# M705ok.net
KiCad netlist of a schematic drawn in EAGLE
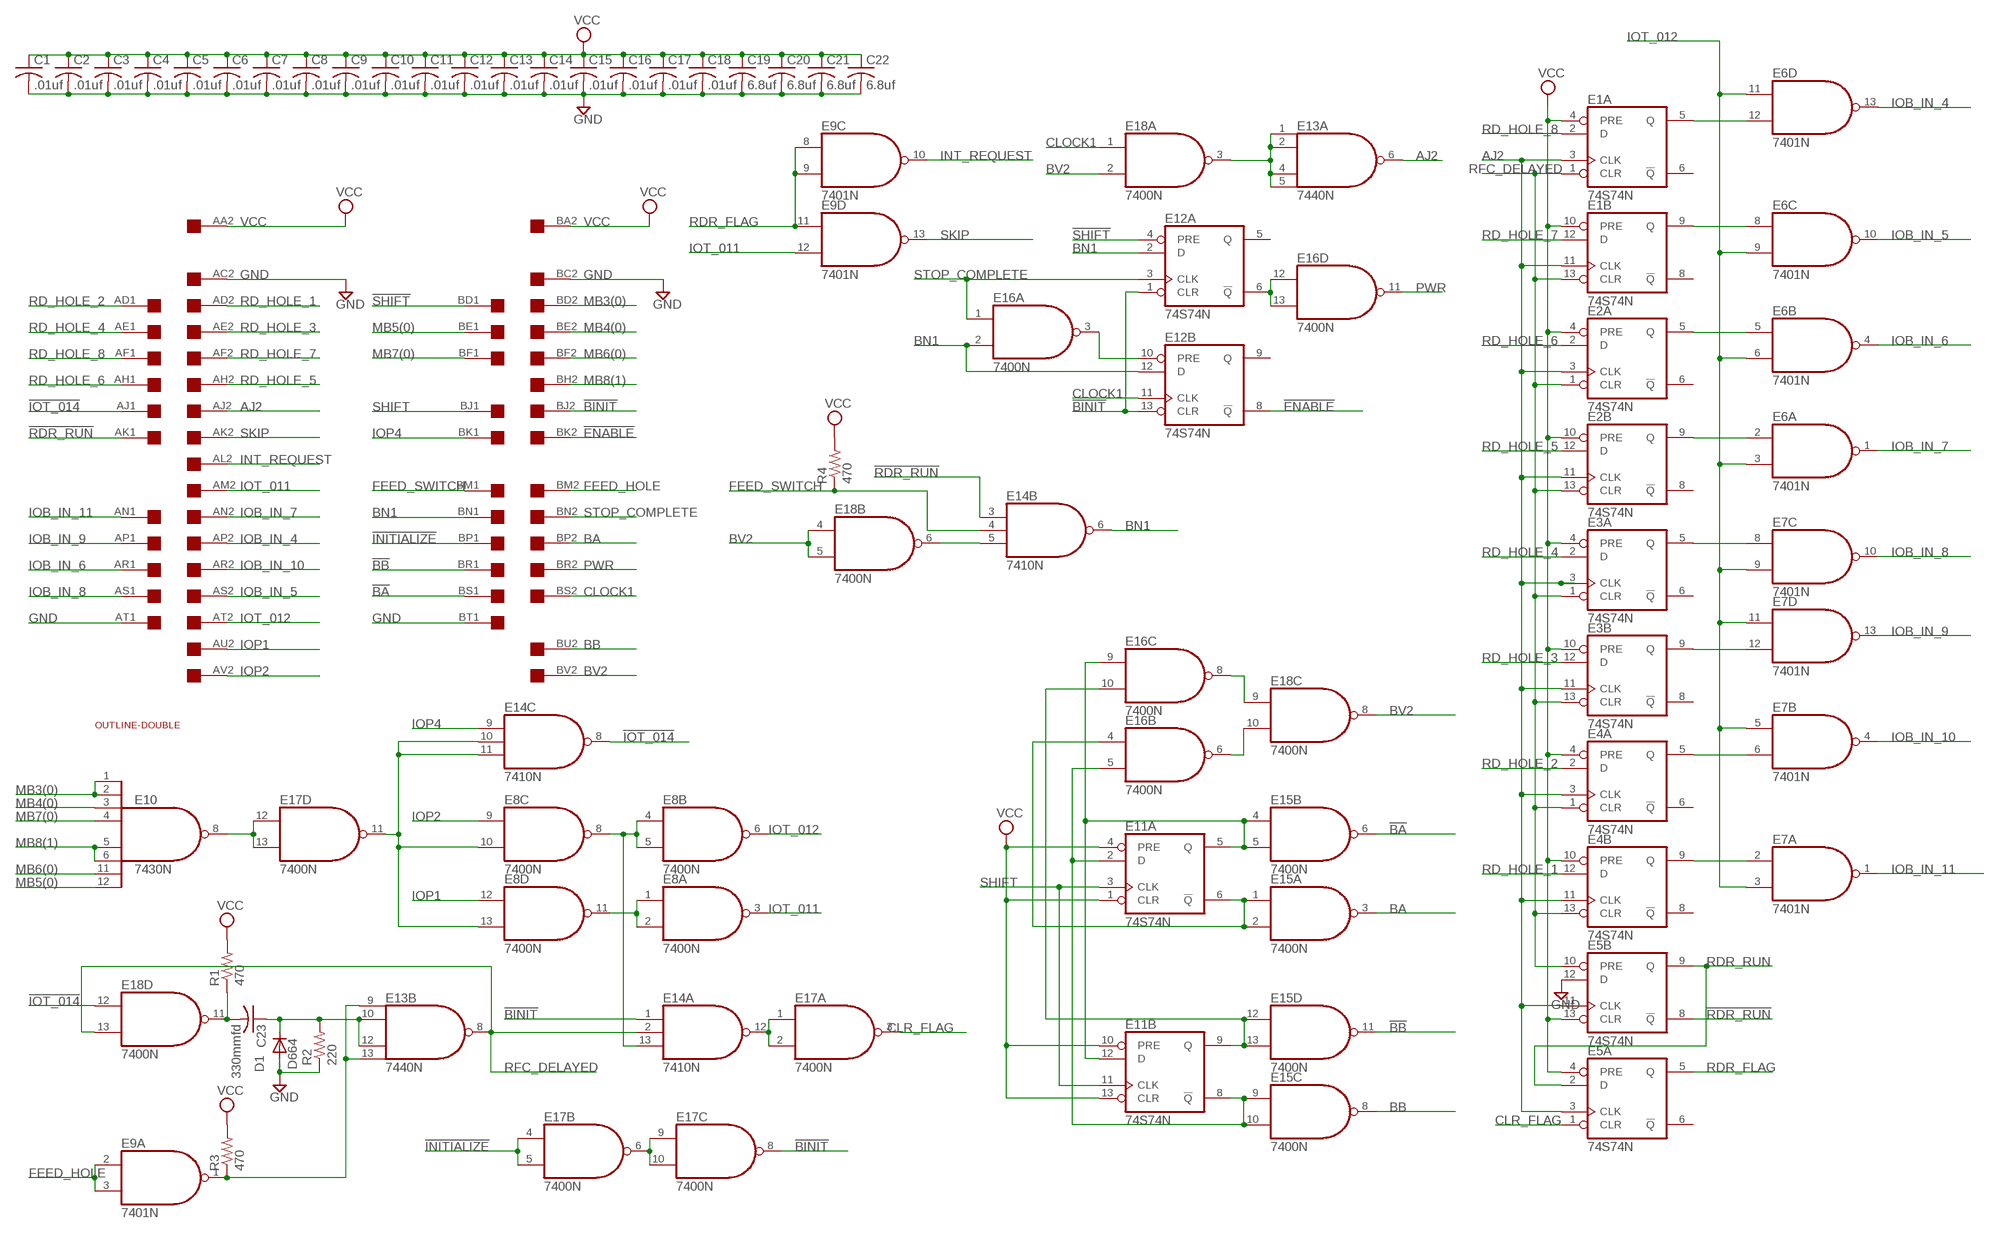
[diagram p0: schematic, sheet 1]

(export (version "E")
  (design (tool "Eeschema 10.0.6"))
  (components
    (comp (ref "C1")
      (value ".01uf")
      (footprint "eagle-import:C050-025X075")
      (libsource (lib "eagle-import") (part "C-US050-025X075"))
    )
    (comp (ref "C2")
      (value ".01uf")
      (footprint "eagle-import:C050-025X075")
      (libsource (lib "eagle-import") (part "C-US050-025X075"))
    )
    (comp (ref "C3")
      (value ".01uf")
      (footprint "eagle-import:C050-025X075")
      (libsource (lib "eagle-import") (part "C-US050-025X075"))
    )
    (comp (ref "C4")
      (value ".01uf")
      (footprint "eagle-import:C050-025X075")
      (libsource (lib "eagle-import") (part "C-US050-025X075"))
    )
    (comp (ref "C5")
      (value ".01uf")
      (footprint "eagle-import:C050-025X075")
      (libsource (lib "eagle-import") (part "C-US050-025X075"))
    )
    (comp (ref "C6")
      (value ".01uf")
      (footprint "eagle-import:C050-025X075")
      (libsource (lib "eagle-import") (part "C-US050-025X075"))
    )
    (comp (ref "C7")
      (value ".01uf")
      (footprint "eagle-import:C050-025X075")
      (libsource (lib "eagle-import") (part "C-US050-025X075"))
    )
    (comp (ref "C8")
      (value ".01uf")
      (footprint "eagle-import:C050-025X075")
      (libsource (lib "eagle-import") (part "C-US050-025X075"))
    )
    (comp (ref "C9")
      (value ".01uf")
      (footprint "eagle-import:C050-025X075")
      (libsource (lib "eagle-import") (part "C-US050-025X075"))
    )
    (comp (ref "C10")
      (value ".01uf")
      (footprint "eagle-import:C050-025X075")
      (libsource (lib "eagle-import") (part "C-US050-025X075"))
    )
    (comp (ref "C11")
      (value ".01uf")
      (footprint "eagle-import:C050-025X075")
      (libsource (lib "eagle-import") (part "C-US050-025X075"))
    )
    (comp (ref "C12")
      (value ".01uf")
      (footprint "eagle-import:C050-025X075")
      (libsource (lib "eagle-import") (part "C-US050-025X075"))
    )
    (comp (ref "C13")
      (value ".01uf")
      (footprint "eagle-import:C050-025X075")
      (libsource (lib "eagle-import") (part "C-US050-025X075"))
    )
    (comp (ref "C14")
      (value ".01uf")
      (footprint "eagle-import:C050-025X075")
      (libsource (lib "eagle-import") (part "C-US050-025X075"))
    )
    (comp (ref "C15")
      (value ".01uf")
      (footprint "eagle-import:C050-025X075")
      (libsource (lib "eagle-import") (part "C-US050-025X075"))
    )
    (comp (ref "C16")
      (value ".01uf")
      (footprint "eagle-import:C050-025X075")
      (libsource (lib "eagle-import") (part "C-US050-025X075"))
    )
    (comp (ref "C17")
      (value ".01uf")
      (footprint "eagle-import:C050-025X075")
      (libsource (lib "eagle-import") (part "C-US050-025X075"))
    )
    (comp (ref "C18")
      (value ".01uf")
      (footprint "eagle-import:C050-025X075")
      (libsource (lib "eagle-import") (part "C-US050-025X075"))
    )
    (comp (ref "C19")
      (value "6.8uf")
      (footprint "eagle-import:C150-054X183")
      (libsource (lib "eagle-import") (part "C-US150-054X183"))
    )
    (comp (ref "C20")
      (value "6.8uf")
      (footprint "eagle-import:C150-054X183")
      (libsource (lib "eagle-import") (part "C-US150-054X183"))
    )
    (comp (ref "C21")
      (value "6.8uf")
      (footprint "eagle-import:C150-054X183")
      (libsource (lib "eagle-import") (part "C-US150-054X183"))
    )
    (comp (ref "C22")
      (value "6.8uf")
      (footprint "eagle-import:C150-054X183")
      (libsource (lib "eagle-import") (part "C-US150-054X183"))
    )
    (comp (ref "C23")
      (value "330mmfd")
      (footprint "eagle-import:C050-025X075")
      (libsource (lib "eagle-import") (part "C-US050-025X075"))
    )
    (comp (ref "D1")
      (value "D664")
      (footprint "eagle-import:DO35-10")
      (libsource (lib "eagle-import") (part "1N4148DO35-10"))
    )
    (comp (ref "E1")
      (value "74S74N")
      (footprint "eagle-import:DIL14")
      (libsource (lib "eagle-import") (part "7474NS"))
    )
    (comp (ref "E2")
      (value "74S74N")
      (footprint "eagle-import:DIL14")
      (libsource (lib "eagle-import") (part "7474NS"))
    )
    (comp (ref "E3")
      (value "74S74N")
      (footprint "eagle-import:DIL14")
      (libsource (lib "eagle-import") (part "7474NS"))
    )
    (comp (ref "E4")
      (value "74S74N")
      (footprint "eagle-import:DIL14")
      (libsource (lib "eagle-import") (part "7474NS"))
    )
    (comp (ref "E5")
      (value "74S74N")
      (footprint "eagle-import:DIL14")
      (libsource (lib "eagle-import") (part "7474NS"))
    )
    (comp (ref "E6")
      (value "7401N")
      (footprint "eagle-import:DIL14")
      (libsource (lib "eagle-import") (part "7401NLS"))
    )
    (comp (ref "E7")
      (value "7401N")
      (footprint "eagle-import:DIL14")
      (libsource (lib "eagle-import") (part "7401NLS"))
    )
    (comp (ref "E8")
      (value "7400N")
      (footprint "eagle-import:DIL14")
      (libsource (lib "eagle-import") (part "7400N"))
    )
    (comp (ref "E9")
      (value "7401N")
      (footprint "eagle-import:DIL14")
      (libsource (lib "eagle-import") (part "7401NLS"))
    )
    (comp (ref "E10")
      (value "7430N")
      (footprint "eagle-import:DIL14")
      (libsource (lib "eagle-import") (part "7430N"))
    )
    (comp (ref "E11")
      (value "74S74N")
      (footprint "eagle-import:DIL14")
      (libsource (lib "eagle-import") (part "7474NS"))
    )
    (comp (ref "E12")
      (value "74S74N")
      (footprint "eagle-import:DIL14")
      (libsource (lib "eagle-import") (part "7474NS"))
    )
    (comp (ref "E13")
      (value "7440N")
      (footprint "eagle-import:DIL14")
      (libsource (lib "eagle-import") (part "7420NS"))
    )
    (comp (ref "E14")
      (value "7410N")
      (footprint "eagle-import:DIL14")
      (libsource (lib "eagle-import") (part "7410N"))
    )
    (comp (ref "E15")
      (value "7400N")
      (footprint "eagle-import:DIL14")
      (libsource (lib "eagle-import") (part "7400N"))
    )
    (comp (ref "E16")
      (value "7400N")
      (footprint "eagle-import:DIL14")
      (libsource (lib "eagle-import") (part "7400N"))
    )
    (comp (ref "E17")
      (value "7400N")
      (footprint "eagle-import:DIL14")
      (libsource (lib "eagle-import") (part "7400N"))
    )
    (comp (ref "E18")
      (value "7400N")
      (footprint "eagle-import:DIL14")
      (libsource (lib "eagle-import") (part "7400N"))
    )
    (comp (ref "R1")
      (value "470")
      (footprint "eagle-import:0207_10")
      (libsource (lib "eagle-import") (part "R-US_0207/10"))
    )
    (comp (ref "R2")
      (value "220")
      (footprint "eagle-import:0207_10")
      (libsource (lib "eagle-import") (part "R-US_0207/10"))
    )
    (comp (ref "R3")
      (value "470")
      (footprint "eagle-import:0207_10")
      (libsource (lib "eagle-import") (part "R-US_0207/10"))
    )
    (comp (ref "R4")
      (value "470")
      (footprint "eagle-import:0207_10")
      (libsource (lib "eagle-import") (part "R-US_0207/10"))
    )
    (comp (ref "U$5")
      (value "DOUBLE")
      (footprint "eagle-import:EDGE-CON4")
      (libsource (lib "eagle-import") (part "DOUBLE"))
    )
    (comp (ref "U$6")
      (value "OUTLINE-DOUBLE")
      (footprint "eagle-import:DOUBLE")
      (libsource (lib "eagle-import") (part "OUTLINE-DOUBLE"))
    )
  )
  (nets
    (net (code "1") (name "/AJ2") (class "Default")
      (node (ref "E1") (pin "11") (pinfunction "CLK_11") (pintype "input"))
      (node (ref "E1") (pin "3") (pinfunction "CLK_3") (pintype "input"))
      (node (ref "E13") (pin "6") (pinfunction "O_6") (pintype "output"))
      (node (ref "E2") (pin "11") (pinfunction "CLK_11") (pintype "input"))
      (node (ref "E2") (pin "3") (pinfunction "CLK_3") (pintype "input"))
      (node (ref "E3") (pin "11") (pinfunction "CLK_11") (pintype "input"))
      (node (ref "E3") (pin "3") (pinfunction "CLK_3") (pintype "input"))
      (node (ref "E4") (pin "11") (pinfunction "CLK_11") (pintype "input"))
      (node (ref "E4") (pin "3") (pinfunction "CLK_3") (pintype "input"))
      (node (ref "E5") (pin "11") (pinfunction "CLK_11") (pintype "input"))
      (node (ref "E5") (pin "3") (pinfunction "CLK_3") (pintype "input"))
      (node (ref "U$5") (pin "AJ2") (pinfunction "1_AJ2") (pintype "bidirectional"))
    )
    (net (code "2") (name "/BA") (class "Default")
      (node (ref "E15") (pin "3") (pinfunction "O_3") (pintype "output"))
      (node (ref "U$5") (pin "BP2") (pinfunction "1_BP2") (pintype "bidirectional"))
    )
    (net (code "3") (name "/BB") (class "Default")
      (node (ref "E15") (pin "8") (pinfunction "O_8") (pintype "output"))
      (node (ref "U$5") (pin "BU2") (pinfunction "1_BU2") (pintype "bidirectional"))
    )
    (net (code "4") (name "/BN1") (class "Default")
      (node (ref "E12") (pin "12") (pinfunction "D_12") (pintype "input"))
      (node (ref "E12") (pin "2") (pinfunction "D_2") (pintype "input"))
      (node (ref "E14") (pin "6") (pinfunction "O_6") (pintype "output"))
      (node (ref "E16") (pin "2") (pinfunction "I1_2") (pintype "input"))
      (node (ref "U$5") (pin "BN1") (pinfunction "1_BN1") (pintype "bidirectional"))
    )
    (net (code "5") (name "/BV2") (class "Default")
      (node (ref "E18") (pin "2") (pinfunction "I1_2") (pintype "input"))
      (node (ref "E18") (pin "4") (pinfunction "I0_4") (pintype "input"))
      (node (ref "E18") (pin "5") (pinfunction "I1_5") (pintype "input"))
      (node (ref "E18") (pin "8") (pinfunction "O_8") (pintype "output"))
      (node (ref "U$5") (pin "BV2") (pinfunction "1_BV2") (pintype "bidirectional"))
    )
    (net (code "6") (name "/CLOCK1") (class "Default")
      (node (ref "E12") (pin "11") (pinfunction "CLK_11") (pintype "input"))
      (node (ref "E18") (pin "1") (pinfunction "I0_1") (pintype "input"))
      (node (ref "U$5") (pin "BS2") (pinfunction "1_BS2") (pintype "bidirectional"))
    )
    (net (code "7") (name "/CLR_FLAG") (class "Default")
      (node (ref "E17") (pin "3") (pinfunction "O_3") (pintype "output"))
      (node (ref "E5") (pin "1") (pinfunction "CLR_1") (pintype "input"))
    )
    (net (code "8") (name "/FEED_HOLE") (class "Default")
      (node (ref "E9") (pin "2") (pinfunction "I0_2") (pintype "input"))
      (node (ref "E9") (pin "3") (pinfunction "I1_3") (pintype "input"))
      (node (ref "U$5") (pin "BM2") (pinfunction "1_BM2") (pintype "bidirectional"))
    )
    (net (code "9") (name "/FEED_SWITCH") (class "Default")
      (node (ref "E14") (pin "4") (pinfunction "I1_4") (pintype "input"))
      (node (ref "R4") (pin "1") (pinfunction "1_1") (pintype "passive"))
      (node (ref "U$5") (pin "BM1") (pinfunction "1_BM1") (pintype "bidirectional"))
    )
    (net (code "10") (name "/INT_REQUEST") (class "Default")
      (node (ref "E9") (pin "10") (pinfunction "O_10") (pintype "open_collector"))
      (node (ref "U$5") (pin "AL2") (pinfunction "1_AL2") (pintype "bidirectional"))
    )
    (net (code "11") (name "/IOB_IN_4") (class "Default")
      (node (ref "E6") (pin "13") (pinfunction "O_13") (pintype "open_collector"))
      (node (ref "U$5") (pin "AP2") (pinfunction "1_AP2") (pintype "bidirectional"))
    )
    (net (code "12") (name "/IOB_IN_5") (class "Default")
      (node (ref "E6") (pin "10") (pinfunction "O_10") (pintype "open_collector"))
      (node (ref "U$5") (pin "AS2") (pinfunction "1_AS2") (pintype "bidirectional"))
    )
    (net (code "13") (name "/IOB_IN_6") (class "Default")
      (node (ref "E6") (pin "4") (pinfunction "O_4") (pintype "open_collector"))
      (node (ref "U$5") (pin "AR1") (pinfunction "1_AR1") (pintype "bidirectional"))
    )
    (net (code "14") (name "/IOB_IN_7") (class "Default")
      (node (ref "E6") (pin "1") (pinfunction "O_1") (pintype "open_collector"))
      (node (ref "U$5") (pin "AN2") (pinfunction "1_AN2") (pintype "bidirectional"))
    )
    (net (code "15") (name "/IOB_IN_8") (class "Default")
      (node (ref "E7") (pin "10") (pinfunction "O_10") (pintype "open_collector"))
      (node (ref "U$5") (pin "AS1") (pinfunction "1_AS1") (pintype "bidirectional"))
    )
    (net (code "16") (name "/IOB_IN_9") (class "Default")
      (node (ref "E7") (pin "13") (pinfunction "O_13") (pintype "open_collector"))
      (node (ref "U$5") (pin "AP1") (pinfunction "1_AP1") (pintype "bidirectional"))
    )
    (net (code "17") (name "/IOB_IN_10") (class "Default")
      (node (ref "E7") (pin "4") (pinfunction "O_4") (pintype "open_collector"))
      (node (ref "U$5") (pin "AR2") (pinfunction "1_AR2") (pintype "bidirectional"))
    )
    (net (code "18") (name "/IOB_IN_11") (class "Default")
      (node (ref "E7") (pin "1") (pinfunction "O_1") (pintype "open_collector"))
      (node (ref "U$5") (pin "AN1") (pinfunction "1_AN1") (pintype "bidirectional"))
    )
    (net (code "19") (name "/IOP1") (class "Default")
      (node (ref "E8") (pin "12") (pinfunction "I0_12") (pintype "input"))
      (node (ref "U$5") (pin "AU2") (pinfunction "1_AU2") (pintype "bidirectional"))
    )
    (net (code "20") (name "/IOP2") (class "Default")
      (node (ref "E8") (pin "9") (pinfunction "I0_9") (pintype "input"))
      (node (ref "U$5") (pin "AV2") (pinfunction "1_AV2") (pintype "bidirectional"))
    )
    (net (code "21") (name "/IOP4") (class "Default")
      (node (ref "E14") (pin "9") (pinfunction "I0_9") (pintype "input"))
      (node (ref "U$5") (pin "BK1") (pinfunction "1_BK1") (pintype "bidirectional"))
    )
    (net (code "22") (name "/IOT_011") (class "Default")
      (node (ref "E8") (pin "3") (pinfunction "O_3") (pintype "output"))
      (node (ref "E9") (pin "12") (pinfunction "I1_12") (pintype "input"))
      (node (ref "U$5") (pin "AM2") (pinfunction "1_AM2") (pintype "bidirectional"))
    )
    (net (code "23") (name "/IOT_012") (class "Default")
      (node (ref "E6") (pin "11") (pinfunction "I0_11") (pintype "input"))
      (node (ref "E6") (pin "3") (pinfunction "I1_3") (pintype "input"))
      (node (ref "E6") (pin "6") (pinfunction "I1_6") (pintype "input"))
      (node (ref "E6") (pin "9") (pinfunction "I1_9") (pintype "input"))
      (node (ref "E7") (pin "11") (pinfunction "I0_11") (pintype "input"))
      (node (ref "E7") (pin "3") (pinfunction "I1_3") (pintype "input"))
      (node (ref "E7") (pin "5") (pinfunction "I0_5") (pintype "input"))
      (node (ref "E7") (pin "9") (pinfunction "I1_9") (pintype "input"))
      (node (ref "E8") (pin "6") (pinfunction "O_6") (pintype "output"))
      (node (ref "U$5") (pin "AT2") (pinfunction "1_AT2") (pintype "bidirectional"))
    )
    (net (code "24") (name "/MB3(0)") (class "Default")
      (node (ref "E10") (pin "1") (pinfunction "I0_1") (pintype "input"))
      (node (ref "E10") (pin "2") (pinfunction "I1_2") (pintype "input"))
      (node (ref "U$5") (pin "BD2") (pinfunction "1_BD2") (pintype "bidirectional"))
    )
    (net (code "25") (name "/MB4(0)") (class "Default")
      (node (ref "E10") (pin "3") (pinfunction "I2_3") (pintype "input"))
      (node (ref "U$5") (pin "BE2") (pinfunction "1_BE2") (pintype "bidirectional"))
    )
    (net (code "26") (name "/MB5(0)") (class "Default")
      (node (ref "E10") (pin "12") (pinfunction "I7_12") (pintype "input"))
      (node (ref "U$5") (pin "BE1") (pinfunction "1_BE1") (pintype "bidirectional"))
    )
    (net (code "27") (name "/MB6(0)") (class "Default")
      (node (ref "E10") (pin "11") (pinfunction "I6_11") (pintype "input"))
      (node (ref "U$5") (pin "BF2") (pinfunction "1_BF2") (pintype "bidirectional"))
    )
    (net (code "28") (name "/MB7(0)") (class "Default")
      (node (ref "E10") (pin "4") (pinfunction "I3_4") (pintype "input"))
      (node (ref "U$5") (pin "BF1") (pinfunction "1_BF1") (pintype "bidirectional"))
    )
    (net (code "29") (name "/MB8(1)") (class "Default")
      (node (ref "E10") (pin "5") (pinfunction "I4_5") (pintype "input"))
      (node (ref "E10") (pin "6") (pinfunction "I5_6") (pintype "input"))
      (node (ref "U$5") (pin "BH2") (pinfunction "1_BH2") (pintype "bidirectional"))
    )
    (net (code "30") (name "/PWR") (class "Default")
      (node (ref "E16") (pin "11") (pinfunction "O_11") (pintype "output"))
      (node (ref "U$5") (pin "BR2") (pinfunction "1_BR2") (pintype "bidirectional"))
    )
    (net (code "31") (name "/RDR_FLAG") (class "Default")
      (node (ref "E5") (pin "5") (pinfunction "Q_5") (pintype "output"))
      (node (ref "E9") (pin "11") (pinfunction "I0_11") (pintype "input"))
      (node (ref "E9") (pin "8") (pinfunction "I0_8") (pintype "input"))
      (node (ref "E9") (pin "9") (pinfunction "I1_9") (pintype "input"))
    )
    (net (code "32") (name "/RDR_RUN") (class "Default")
      (node (ref "E5") (pin "2") (pinfunction "D_2") (pintype "input"))
      (node (ref "E5") (pin "9") (pinfunction "Q_9") (pintype "output"))
    )
    (net (code "33") (name "/RD_HOLE_1") (class "Default")
      (node (ref "E4") (pin "12") (pinfunction "D_12") (pintype "input"))
      (node (ref "U$5") (pin "AD2") (pinfunction "1_AD2") (pintype "bidirectional"))
    )
    (net (code "34") (name "/RD_HOLE_2") (class "Default")
      (node (ref "E4") (pin "2") (pinfunction "D_2") (pintype "input"))
      (node (ref "U$5") (pin "AD1") (pinfunction "1_AD1") (pintype "bidirectional"))
    )
    (net (code "35") (name "/RD_HOLE_3") (class "Default")
      (node (ref "E3") (pin "12") (pinfunction "D_12") (pintype "input"))
      (node (ref "U$5") (pin "AE2") (pinfunction "1_AE2") (pintype "bidirectional"))
    )
    (net (code "36") (name "/RD_HOLE_4") (class "Default")
      (node (ref "E3") (pin "2") (pinfunction "D_2") (pintype "input"))
      (node (ref "U$5") (pin "AE1") (pinfunction "1_AE1") (pintype "bidirectional"))
    )
    (net (code "37") (name "/RD_HOLE_5") (class "Default")
      (node (ref "E2") (pin "12") (pinfunction "D_12") (pintype "input"))
      (node (ref "U$5") (pin "AH2") (pinfunction "1_AH2") (pintype "bidirectional"))
    )
    (net (code "38") (name "/RD_HOLE_6") (class "Default")
      (node (ref "E2") (pin "2") (pinfunction "D_2") (pintype "input"))
      (node (ref "U$5") (pin "AH1") (pinfunction "1_AH1") (pintype "bidirectional"))
    )
    (net (code "39") (name "/RD_HOLE_7") (class "Default")
      (node (ref "E1") (pin "12") (pinfunction "D_12") (pintype "input"))
      (node (ref "U$5") (pin "AF2") (pinfunction "1_AF2") (pintype "bidirectional"))
    )
    (net (code "40") (name "/RD_HOLE_8") (class "Default")
      (node (ref "E1") (pin "2") (pinfunction "D_2") (pintype "input"))
      (node (ref "U$5") (pin "AF1") (pinfunction "1_AF1") (pintype "bidirectional"))
    )
    (net (code "41") (name "/RFC_DELAYED") (class "Default")
      (node (ref "E1") (pin "1") (pinfunction "CLR_1") (pintype "input"))
      (node (ref "E1") (pin "13") (pinfunction "CLR_13") (pintype "input"))
      (node (ref "E13") (pin "8") (pinfunction "O_8") (pintype "output"))
      (node (ref "E14") (pin "2") (pinfunction "I1_2") (pintype "input"))
      (node (ref "E18") (pin "13") (pinfunction "I1_13") (pintype "input"))
      (node (ref "E2") (pin "1") (pinfunction "CLR_1") (pintype "input"))
      (node (ref "E2") (pin "13") (pinfunction "CLR_13") (pintype "input"))
      (node (ref "E3") (pin "1") (pinfunction "CLR_1") (pintype "input"))
      (node (ref "E3") (pin "13") (pinfunction "CLR_13") (pintype "input"))
      (node (ref "E4") (pin "1") (pinfunction "CLR_1") (pintype "input"))
      (node (ref "E4") (pin "13") (pinfunction "CLR_13") (pintype "input"))
      (node (ref "E5") (pin "10") (pinfunction "PRE_10") (pintype "input"))
    )
    (net (code "42") (name "/SHIFT") (class "Default")
      (node (ref "E11") (pin "11") (pinfunction "CLK_11") (pintype "input"))
      (node (ref "E11") (pin "3") (pinfunction "CLK_3") (pintype "input"))
      (node (ref "U$5") (pin "BJ1") (pinfunction "1_BJ1") (pintype "bidirectional"))
    )
    (net (code "43") (name "/SKIP") (class "Default")
      (node (ref "E9") (pin "13") (pinfunction "O_13") (pintype "open_collector"))
      (node (ref "U$5") (pin "AK2") (pinfunction "1_AK2") (pintype "bidirectional"))
    )
    (net (code "44") (name "/STOP_COMPLETE") (class "Default")
      (node (ref "E12") (pin "3") (pinfunction "CLK_3") (pintype "input"))
      (node (ref "E16") (pin "1") (pinfunction "I0_1") (pintype "input"))
      (node (ref "U$5") (pin "BN2") (pinfunction "1_BN2") (pintype "bidirectional"))
    )
    (net (code "45") (name "/~{BA}") (class "Default")
      (node (ref "E15") (pin "6") (pinfunction "O_6") (pintype "output"))
      (node (ref "U$5") (pin "BS1") (pinfunction "1_BS1") (pintype "bidirectional"))
    )
    (net (code "46") (name "/~{BB}") (class "Default")
      (node (ref "E15") (pin "11") (pinfunction "O_11") (pintype "output"))
      (node (ref "U$5") (pin "BR1") (pinfunction "1_BR1") (pintype "bidirectional"))
    )
    (net (code "47") (name "/~{BINIT}") (class "Default")
      (node (ref "E12") (pin "1") (pinfunction "CLR_1") (pintype "input"))
      (node (ref "E12") (pin "13") (pinfunction "CLR_13") (pintype "input"))
      (node (ref "E14") (pin "1") (pinfunction "I0_1") (pintype "input"))
      (node (ref "E17") (pin "8") (pinfunction "O_8") (pintype "output"))
      (node (ref "U$5") (pin "BJ2") (pinfunction "1_BJ2") (pintype "bidirectional"))
    )
    (net (code "48") (name "/~{ENABLE}") (class "Default")
      (node (ref "E12") (pin "8") (pinfunction "~{Q}_8") (pintype "output"))
      (node (ref "U$5") (pin "BK2") (pinfunction "1_BK2") (pintype "bidirectional"))
    )
    (net (code "49") (name "/~{INITIALIZE}") (class "Default")
      (node (ref "E17") (pin "4") (pinfunction "I0_4") (pintype "input"))
      (node (ref "E17") (pin "5") (pinfunction "I1_5") (pintype "input"))
      (node (ref "U$5") (pin "BP1") (pinfunction "1_BP1") (pintype "bidirectional"))
    )
    (net (code "50") (name "/~{IOT_014}") (class "Default")
      (node (ref "E14") (pin "8") (pinfunction "O_8") (pintype "output"))
      (node (ref "E18") (pin "12") (pinfunction "I0_12") (pintype "input"))
      (node (ref "U$5") (pin "AJ1") (pinfunction "1_AJ1") (pintype "bidirectional"))
    )
    (net (code "51") (name "/~{RDR_RUN}") (class "Default")
      (node (ref "E14") (pin "3") (pinfunction "I0_3") (pintype "input"))
      (node (ref "E5") (pin "8") (pinfunction "~{Q}_8") (pintype "output"))
      (node (ref "U$5") (pin "AK1") (pinfunction "1_AK1") (pintype "bidirectional"))
    )
    (net (code "52") (name "/~{SHIFT}") (class "Default")
      (node (ref "E12") (pin "4") (pinfunction "PRE_4") (pintype "input"))
      (node (ref "U$5") (pin "BD1") (pinfunction "1_BD1") (pintype "bidirectional"))
    )
    (net (code "53") (name "GND") (class "Default")
      (node (ref "C1") (pin "2") (pinfunction "2_2") (pintype "passive"))
      (node (ref "C10") (pin "2") (pinfunction "2_2") (pintype "passive"))
      (node (ref "C11") (pin "2") (pinfunction "2_2") (pintype "passive"))
      (node (ref "C12") (pin "2") (pinfunction "2_2") (pintype "passive"))
      (node (ref "C13") (pin "2") (pinfunction "2_2") (pintype "passive"))
      (node (ref "C14") (pin "2") (pinfunction "2_2") (pintype "passive"))
      (node (ref "C15") (pin "2") (pinfunction "2_2") (pintype "passive"))
      (node (ref "C16") (pin "2") (pinfunction "2_2") (pintype "passive"))
      (node (ref "C17") (pin "2") (pinfunction "2_2") (pintype "passive"))
      (node (ref "C18") (pin "2") (pinfunction "2_2") (pintype "passive"))
      (node (ref "C19") (pin "2") (pinfunction "2_2") (pintype "passive"))
      (node (ref "C2") (pin "2") (pinfunction "2_2") (pintype "passive"))
      (node (ref "C20") (pin "2") (pinfunction "2_2") (pintype "passive"))
      (node (ref "C21") (pin "2") (pinfunction "2_2") (pintype "passive"))
      (node (ref "C22") (pin "2") (pinfunction "2_2") (pintype "passive"))
      (node (ref "C3") (pin "2") (pinfunction "2_2") (pintype "passive"))
      (node (ref "C4") (pin "2") (pinfunction "2_2") (pintype "passive"))
      (node (ref "C5") (pin "2") (pinfunction "2_2") (pintype "passive"))
      (node (ref "C6") (pin "2") (pinfunction "2_2") (pintype "passive"))
      (node (ref "C7") (pin "2") (pinfunction "2_2") (pintype "passive"))
      (node (ref "C8") (pin "2") (pinfunction "2_2") (pintype "passive"))
      (node (ref "C9") (pin "2") (pinfunction "2_2") (pintype "passive"))
      (node (ref "D1") (pin "A") (pinfunction "A_A") (pintype "passive"))
      (node (ref "E5") (pin "12") (pinfunction "D_12") (pintype "input"))
      (node (ref "R2") (pin "1") (pinfunction "1_1") (pintype "passive"))
      (node (ref "U$5") (pin "AC2") (pinfunction "1_AC2") (pintype "bidirectional"))
      (node (ref "U$5") (pin "AT1") (pinfunction "1_AT1") (pintype "bidirectional"))
      (node (ref "U$5") (pin "BC2") (pinfunction "1_BC2") (pintype "bidirectional"))
      (node (ref "U$5") (pin "BT1") (pinfunction "1_BT1") (pintype "bidirectional"))
    )
    (net (code "54") (name "Net-(E1A-Q)") (class "Default")
      (node (ref "E1") (pin "5") (pinfunction "Q_5") (pintype "output"))
      (node (ref "E6") (pin "12") (pinfunction "I1_12") (pintype "input"))
    )
    (net (code "55") (name "Net-(E1B-Q)") (class "Default")
      (node (ref "E1") (pin "9") (pinfunction "Q_9") (pintype "output"))
      (node (ref "E6") (pin "8") (pinfunction "I0_8") (pintype "input"))
    )
    (net (code "56") (name "Net-(E2A-Q)") (class "Default")
      (node (ref "E2") (pin "5") (pinfunction "Q_5") (pintype "output"))
      (node (ref "E6") (pin "5") (pinfunction "I0_5") (pintype "input"))
    )
    (net (code "57") (name "Net-(E2B-Q)") (class "Default")
      (node (ref "E2") (pin "9") (pinfunction "Q_9") (pintype "output"))
      (node (ref "E6") (pin "2") (pinfunction "I0_2") (pintype "input"))
    )
    (net (code "58") (name "Net-(E3A-Q)") (class "Default")
      (node (ref "E3") (pin "5") (pinfunction "Q_5") (pintype "output"))
      (node (ref "E7") (pin "8") (pinfunction "I0_8") (pintype "input"))
    )
    (net (code "59") (name "Net-(E3B-Q)") (class "Default")
      (node (ref "E3") (pin "9") (pinfunction "Q_9") (pintype "output"))
      (node (ref "E7") (pin "12") (pinfunction "I1_12") (pintype "input"))
    )
    (net (code "60") (name "Net-(E4A-Q)") (class "Default")
      (node (ref "E4") (pin "5") (pinfunction "Q_5") (pintype "output"))
      (node (ref "E7") (pin "6") (pinfunction "I1_6") (pintype "input"))
    )
    (net (code "61") (name "Net-(E4B-Q)") (class "Default")
      (node (ref "E4") (pin "9") (pinfunction "Q_9") (pintype "output"))
      (node (ref "E7") (pin "2") (pinfunction "I0_2") (pintype "input"))
    )
    (net (code "62") (name "Net-(E8A-I0)") (class "Default")
      (node (ref "E8") (pin "1") (pinfunction "I0_1") (pintype "input"))
      (node (ref "E8") (pin "11") (pinfunction "O_11") (pintype "output"))
      (node (ref "E8") (pin "2") (pinfunction "I1_2") (pintype "input"))
    )
    (net (code "63") (name "Net-(E10A-O)") (class "Default")
      (node (ref "E10") (pin "8") (pinfunction "O_8") (pintype "output"))
      (node (ref "E17") (pin "12") (pinfunction "I0_12") (pintype "input"))
      (node (ref "E17") (pin "13") (pinfunction "I1_13") (pintype "input"))
    )
    (net (code "64") (name "Net-(E11A-D)") (class "Default")
      (node (ref "E11") (pin "2") (pinfunction "D_2") (pintype "input"))
      (node (ref "E11") (pin "8") (pinfunction "~{Q}_8") (pintype "output"))
      (node (ref "E15") (pin "10") (pinfunction "I1_10") (pintype "input"))
      (node (ref "E15") (pin "9") (pinfunction "I0_9") (pintype "input"))
      (node (ref "E16") (pin "5") (pinfunction "I1_5") (pintype "input"))
    )
    (net (code "65") (name "Net-(E11A-Q)") (class "Default")
      (node (ref "E11") (pin "12") (pinfunction "D_12") (pintype "input"))
      (node (ref "E11") (pin "5") (pinfunction "Q_5") (pintype "output"))
      (node (ref "E15") (pin "4") (pinfunction "I0_4") (pintype "input"))
      (node (ref "E15") (pin "5") (pinfunction "I1_5") (pintype "input"))
      (node (ref "E16") (pin "9") (pinfunction "I0_9") (pintype "input"))
    )
    (net (code "66") (name "Net-(E11A-~{Q})") (class "Default")
      (node (ref "E11") (pin "6") (pinfunction "~{Q}_6") (pintype "output"))
      (node (ref "E15") (pin "1") (pinfunction "I0_1") (pintype "input"))
      (node (ref "E15") (pin "2") (pinfunction "I1_2") (pintype "input"))
      (node (ref "E16") (pin "4") (pinfunction "I0_4") (pintype "input"))
    )
    (net (code "67") (name "Net-(E11B-Q)") (class "Default")
      (node (ref "E11") (pin "9") (pinfunction "Q_9") (pintype "output"))
      (node (ref "E15") (pin "12") (pinfunction "I0_12") (pintype "input"))
      (node (ref "E15") (pin "13") (pinfunction "I1_13") (pintype "input"))
      (node (ref "E16") (pin "10") (pinfunction "I1_10") (pintype "input"))
    )
    (net (code "68") (name "Net-(E12A-~{Q})") (class "Default")
      (node (ref "E12") (pin "6") (pinfunction "~{Q}_6") (pintype "output"))
      (node (ref "E16") (pin "12") (pinfunction "I0_12") (pintype "input"))
      (node (ref "E16") (pin "13") (pinfunction "I1_13") (pintype "input"))
    )
    (net (code "69") (name "Net-(E12B-PRE)") (class "Default")
      (node (ref "E12") (pin "10") (pinfunction "PRE_10") (pintype "input"))
      (node (ref "E16") (pin "3") (pinfunction "O_3") (pintype "output"))
    )
    (net (code "70") (name "Net-(E13A-I0)") (class "Default")
      (node (ref "E13") (pin "1") (pinfunction "I0_1") (pintype "input"))
      (node (ref "E13") (pin "2") (pinfunction "I1_2") (pintype "input"))
      (node (ref "E13") (pin "4") (pinfunction "I2_4") (pintype "input"))
      (node (ref "E13") (pin "5") (pinfunction "I3_5") (pintype "input"))
      (node (ref "E18") (pin "3") (pinfunction "O_3") (pintype "output"))
    )
    (net (code "71") (name "Net-(E13B-I0)") (class "Default")
      (node (ref "E13") (pin "13") (pinfunction "I3_13") (pintype "input"))
      (node (ref "E13") (pin "9") (pinfunction "I0_9") (pintype "input"))
      (node (ref "E9") (pin "1") (pinfunction "O_1") (pintype "open_collector"))
      (node (ref "R3") (pin "1") (pinfunction "1_1") (pintype "passive"))
    )
    (net (code "72") (name "Net-(E13B-I1)") (class "Default")
      (node (ref "C23") (pin "1") (pinfunction "1_1") (pintype "passive"))
      (node (ref "D1") (pin "C") (pinfunction "C_C") (pintype "passive"))
      (node (ref "E13") (pin "10") (pinfunction "I1_10") (pintype "input"))
      (node (ref "E13") (pin "12") (pinfunction "I2_12") (pintype "input"))
      (node (ref "R2") (pin "2") (pinfunction "2_2") (pintype "passive"))
    )
    (net (code "73") (name "Net-(E14A-I2)") (class "Default")
      (node (ref "E14") (pin "13") (pinfunction "I2_13") (pintype "input"))
      (node (ref "E8") (pin "4") (pinfunction "I0_4") (pintype "input"))
      (node (ref "E8") (pin "5") (pinfunction "I1_5") (pintype "input"))
      (node (ref "E8") (pin "8") (pinfunction "O_8") (pintype "output"))
    )
    (net (code "74") (name "Net-(E14A-O)") (class "Default")
      (node (ref "E14") (pin "12") (pinfunction "O_12") (pintype "output"))
      (node (ref "E17") (pin "1") (pinfunction "I0_1") (pintype "input"))
      (node (ref "E17") (pin "2") (pinfunction "I1_2") (pintype "input"))
    )
    (net (code "75") (name "Net-(E14B-I2)") (class "Default")
      (node (ref "E14") (pin "5") (pinfunction "I2_5") (pintype "input"))
      (node (ref "E18") (pin "6") (pinfunction "O_6") (pintype "output"))
    )
    (net (code "76") (name "Net-(E14C-I1)") (class "Default")
      (node (ref "E14") (pin "10") (pinfunction "I1_10") (pintype "input"))
      (node (ref "E14") (pin "11") (pinfunction "I2_11") (pintype "input"))
      (node (ref "E17") (pin "11") (pinfunction "O_11") (pintype "output"))
      (node (ref "E8") (pin "10") (pinfunction "I1_10") (pintype "input"))
      (node (ref "E8") (pin "13") (pinfunction "I1_13") (pintype "input"))
    )
    (net (code "77") (name "Net-(E16B-O)") (class "Default")
      (node (ref "E16") (pin "6") (pinfunction "O_6") (pintype "output"))
      (node (ref "E18") (pin "10") (pinfunction "I1_10") (pintype "input"))
    )
    (net (code "78") (name "Net-(E16C-O)") (class "Default")
      (node (ref "E16") (pin "8") (pinfunction "O_8") (pintype "output"))
      (node (ref "E18") (pin "9") (pinfunction "I0_9") (pintype "input"))
    )
    (net (code "79") (name "Net-(E17B-O)") (class "Default")
      (node (ref "E17") (pin "10") (pinfunction "I1_10") (pintype "input"))
      (node (ref "E17") (pin "6") (pinfunction "O_6") (pintype "output"))
      (node (ref "E17") (pin "9") (pinfunction "I0_9") (pintype "input"))
    )
    (net (code "80") (name "Net-(E18D-O)") (class "Default")
      (node (ref "C23") (pin "2") (pinfunction "2_2") (pintype "passive"))
      (node (ref "E18") (pin "11") (pinfunction "O_11") (pintype "output"))
      (node (ref "R1") (pin "1") (pinfunction "1_1") (pintype "passive"))
    )
    (net (code "81") (name "VCC") (class "Default")
      (node (ref "C1") (pin "1") (pinfunction "1_1") (pintype "passive"))
      (node (ref "C10") (pin "1") (pinfunction "1_1") (pintype "passive"))
      (node (ref "C11") (pin "1") (pinfunction "1_1") (pintype "passive"))
      (node (ref "C12") (pin "1") (pinfunction "1_1") (pintype "passive"))
      (node (ref "C13") (pin "1") (pinfunction "1_1") (pintype "passive"))
      (node (ref "C14") (pin "1") (pinfunction "1_1") (pintype "passive"))
      (node (ref "C15") (pin "1") (pinfunction "1_1") (pintype "passive"))
      (node (ref "C16") (pin "1") (pinfunction "1_1") (pintype "passive"))
      (node (ref "C17") (pin "1") (pinfunction "1_1") (pintype "passive"))
      (node (ref "C18") (pin "1") (pinfunction "1_1") (pintype "passive"))
      (node (ref "C19") (pin "1") (pinfunction "1_1") (pintype "passive"))
      (node (ref "C2") (pin "1") (pinfunction "1_1") (pintype "passive"))
      (node (ref "C20") (pin "1") (pinfunction "1_1") (pintype "passive"))
      (node (ref "C21") (pin "1") (pinfunction "1_1") (pintype "passive"))
      (node (ref "C22") (pin "1") (pinfunction "1_1") (pintype "passive"))
      (node (ref "C3") (pin "1") (pinfunction "1_1") (pintype "passive"))
      (node (ref "C4") (pin "1") (pinfunction "1_1") (pintype "passive"))
      (node (ref "C5") (pin "1") (pinfunction "1_1") (pintype "passive"))
      (node (ref "C6") (pin "1") (pinfunction "1_1") (pintype "passive"))
      (node (ref "C7") (pin "1") (pinfunction "1_1") (pintype "passive"))
      (node (ref "C8") (pin "1") (pinfunction "1_1") (pintype "passive"))
      (node (ref "C9") (pin "1") (pinfunction "1_1") (pintype "passive"))
      (node (ref "E1") (pin "10") (pinfunction "PRE_10") (pintype "input"))
      (node (ref "E1") (pin "4") (pinfunction "PRE_4") (pintype "input"))
      (node (ref "E11") (pin "1") (pinfunction "CLR_1") (pintype "input"))
      (node (ref "E11") (pin "10") (pinfunction "PRE_10") (pintype "input"))
      (node (ref "E11") (pin "13") (pinfunction "CLR_13") (pintype "input"))
      (node (ref "E11") (pin "4") (pinfunction "PRE_4") (pintype "input"))
      (node (ref "E2") (pin "10") (pinfunction "PRE_10") (pintype "input"))
      (node (ref "E2") (pin "4") (pinfunction "PRE_4") (pintype "input"))
      (node (ref "E3") (pin "10") (pinfunction "PRE_10") (pintype "input"))
      (node (ref "E3") (pin "4") (pinfunction "PRE_4") (pintype "input"))
      (node (ref "E4") (pin "10") (pinfunction "PRE_10") (pintype "input"))
      (node (ref "E4") (pin "4") (pinfunction "PRE_4") (pintype "input"))
      (node (ref "E5") (pin "13") (pinfunction "CLR_13") (pintype "input"))
      (node (ref "E5") (pin "4") (pinfunction "PRE_4") (pintype "input"))
      (node (ref "R1") (pin "2") (pinfunction "2_2") (pintype "passive"))
      (node (ref "R3") (pin "2") (pinfunction "2_2") (pintype "passive"))
      (node (ref "R4") (pin "2") (pinfunction "2_2") (pintype "passive"))
      (node (ref "U$5") (pin "AA2") (pinfunction "1_AA2") (pintype "bidirectional"))
      (node (ref "U$5") (pin "BA2") (pinfunction "1_BA2") (pintype "bidirectional"))
    )
    (net (code "82") (name "unconnected-(E1A-~{Q}-Pad6)") (class "Default")
      (node (ref "E1") (pin "6") (pinfunction "~{Q}_6") (pintype "output"))
    )
    (net (code "83") (name "unconnected-(E1B-~{Q}-Pad8)") (class "Default")
      (node (ref "E1") (pin "8") (pinfunction "~{Q}_8") (pintype "output"))
    )
    (net (code "84") (name "unconnected-(E2A-~{Q}-Pad6)") (class "Default")
      (node (ref "E2") (pin "6") (pinfunction "~{Q}_6") (pintype "output"))
    )
    (net (code "85") (name "unconnected-(E2B-~{Q}-Pad8)") (class "Default")
      (node (ref "E2") (pin "8") (pinfunction "~{Q}_8") (pintype "output"))
    )
    (net (code "86") (name "unconnected-(E3A-~{Q}-Pad6)") (class "Default")
      (node (ref "E3") (pin "6") (pinfunction "~{Q}_6") (pintype "output"))
    )
    (net (code "87") (name "unconnected-(E3B-~{Q}-Pad8)") (class "Default")
      (node (ref "E3") (pin "8") (pinfunction "~{Q}_8") (pintype "output"))
    )
    (net (code "88") (name "unconnected-(E4A-~{Q}-Pad6)") (class "Default")
      (node (ref "E4") (pin "6") (pinfunction "~{Q}_6") (pintype "output"))
    )
    (net (code "89") (name "unconnected-(E4B-~{Q}-Pad8)") (class "Default")
      (node (ref "E4") (pin "8") (pinfunction "~{Q}_8") (pintype "output"))
    )
    (net (code "90") (name "unconnected-(E5A-~{Q}-Pad6)") (class "Default")
      (node (ref "E5") (pin "6") (pinfunction "~{Q}_6") (pintype "output"))
    )
    (net (code "91") (name "unconnected-(E12A-Q-Pad5)") (class "Default")
      (node (ref "E12") (pin "5") (pinfunction "Q_5") (pintype "output"))
    )
    (net (code "92") (name "unconnected-(E12B-Q-Pad9)") (class "Default")
      (node (ref "E12") (pin "9") (pinfunction "Q_9") (pintype "output"))
    )
  )
)
